# Raspberry_Pi_CM4_Periphery.net
KiCad netlist of a schematic drawn in Altium Designer
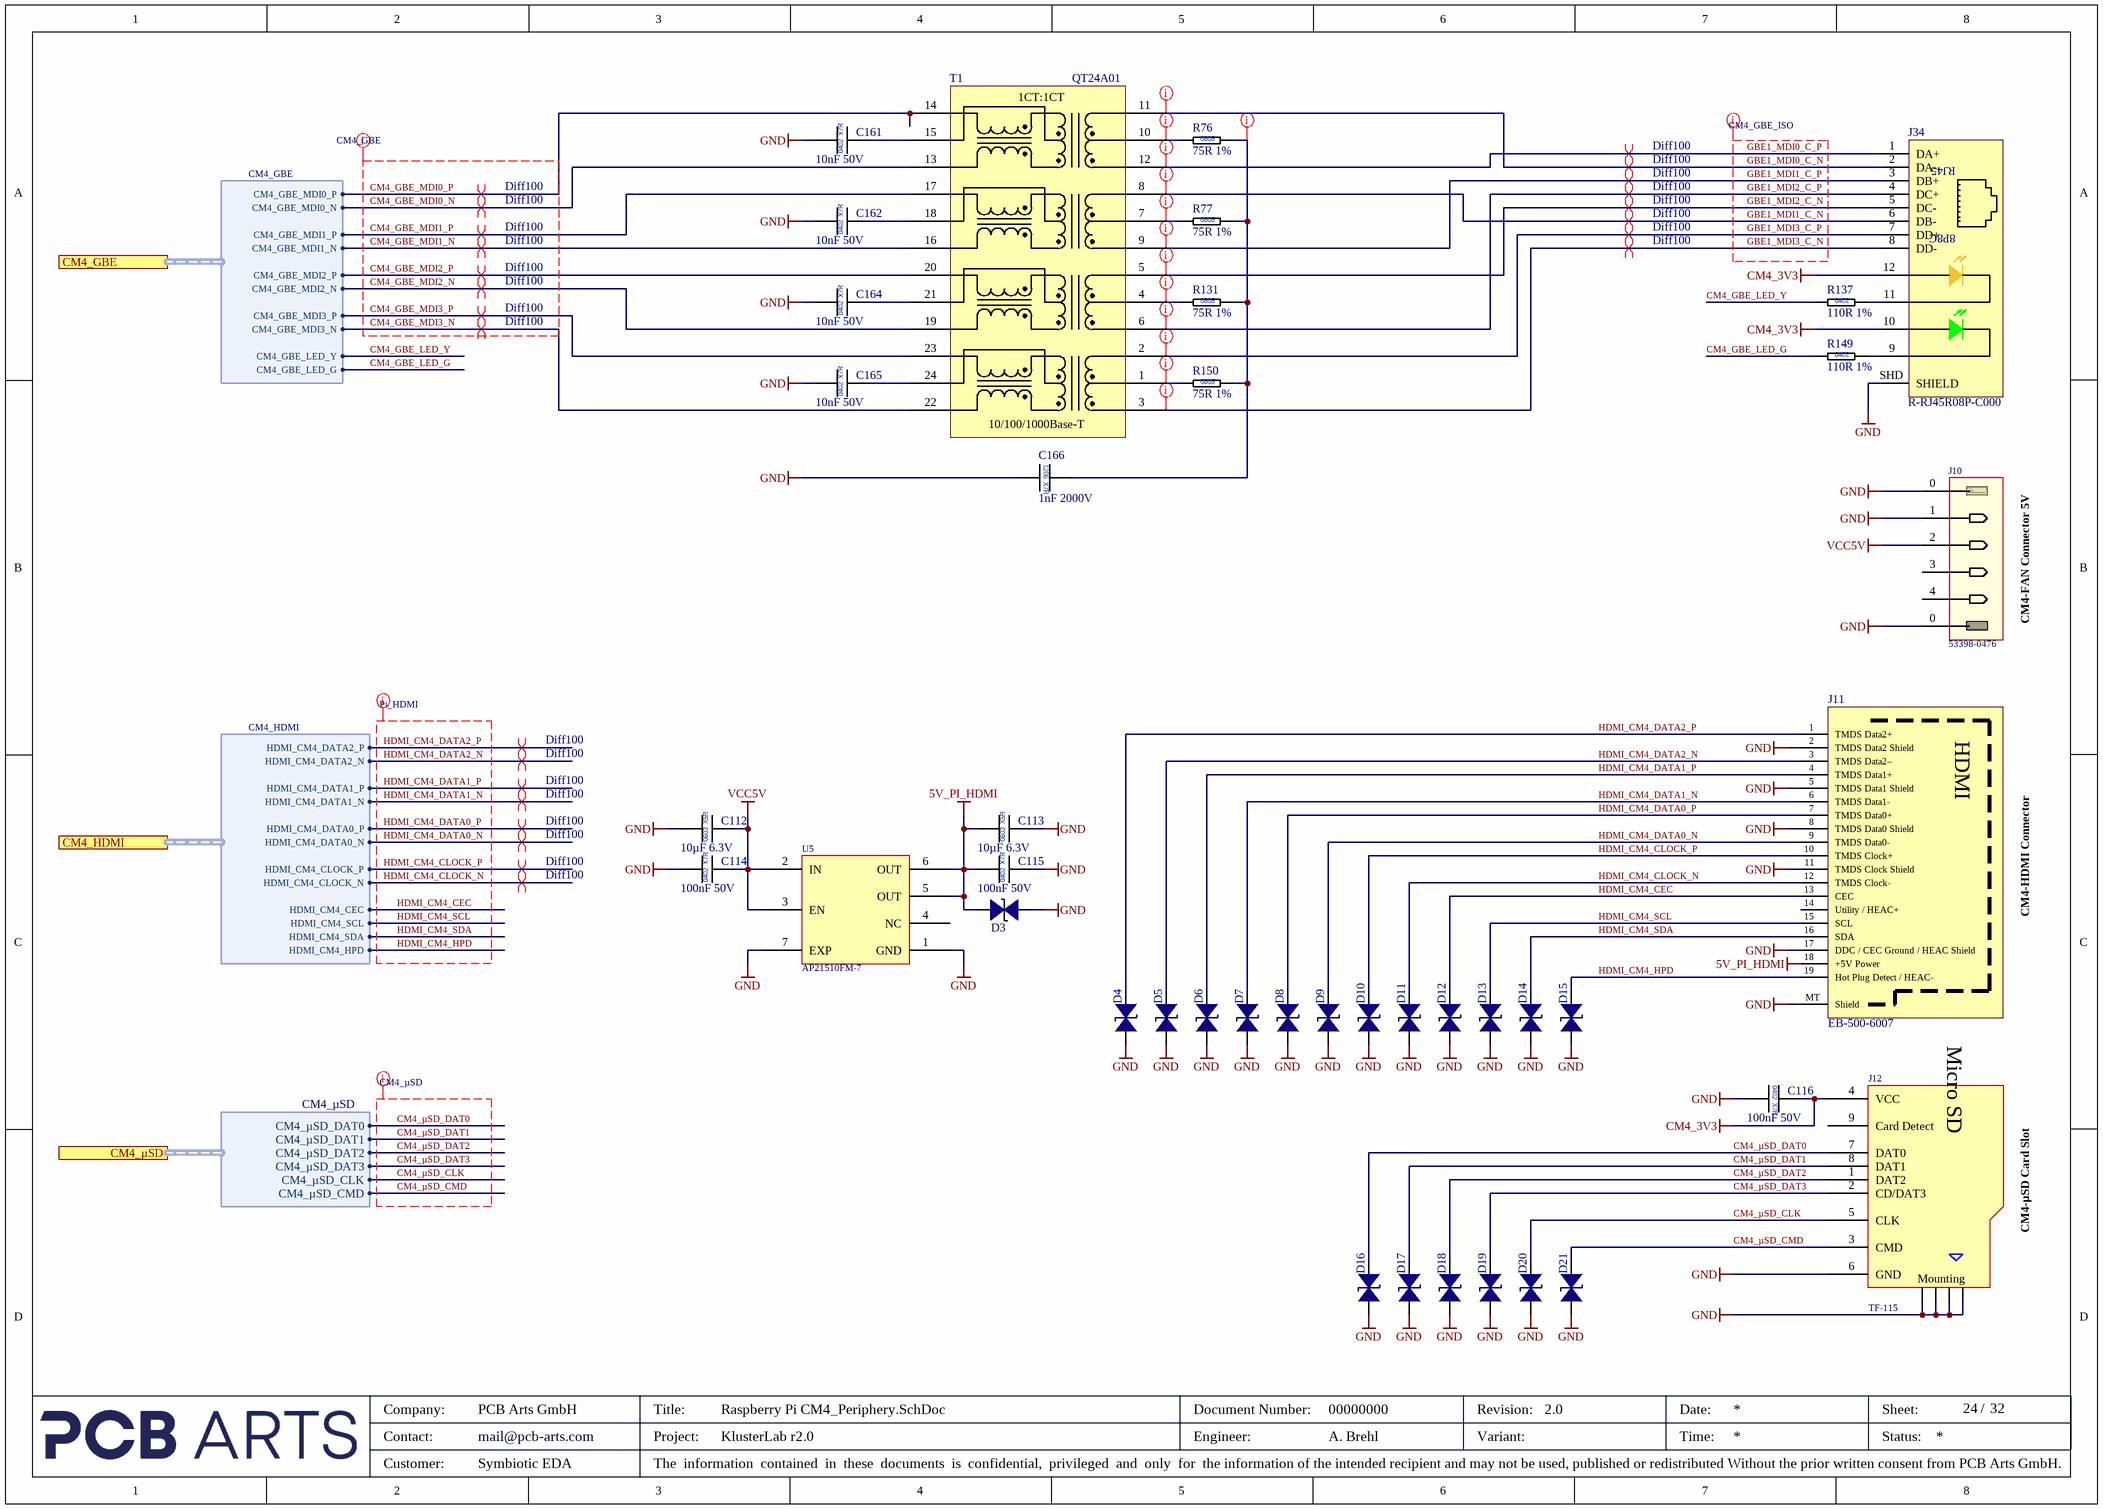
[diagram p0: Raspberry Pi CM4_Periphery.SchDoc]

(export (version "E")
  (design (tool "Eeschema 10.0.6"))
  (components
    (comp (ref "C112")
      (value "10µF 6.3V")
      (footprint "Cap:CAP_0603_L")
      (description "Multilayer Ceramic Capacitors MLCC - SMD/SMT 0603 6.3VDC")
      (libsource (lib "Cap") (part "CAP_0603_10µF_6.3V"))
    )
    (comp (ref "C113")
      (value "10µF 6.3V")
      (footprint "Cap:CAP_0603_L")
      (description "Multilayer Ceramic Capacitors MLCC - SMD/SMT 0603 6.3VDC")
      (libsource (lib "Cap") (part "CAP_0603_10µF_6.3V"))
    )
    (comp (ref "C114")
      (value "100nF 50V")
      (footprint "Cap:CAP_0402_L")
      (description "Multilayer Ceramic Capacitors MLCC - SMD/SMT 0402 50VDC")
      (libsource (lib "Cap") (part "CAP_0402_100nF_50V"))
    )
    (comp (ref "C115")
      (value "100nF 50V")
      (footprint "Cap:CAP_0402_L")
      (description "Multilayer Ceramic Capacitors MLCC - SMD/SMT 0402 50VDC")
      (libsource (lib "Cap") (part "CAP_0402_100nF_50V"))
    )
    (comp (ref "C116")
      (value "100nF 50V")
      (footprint "Cap:CAP_0402_L")
      (description "Multilayer Ceramic Capacitors MLCC - SMD/SMT 0402 50VDC")
      (libsource (lib "") (part "CAP_0402_100nF_50V_1"))
    )
    (comp (ref "C161")
      (value "10nF 50V")
      (footprint "Cap:CAP_0402_L")
      (description "Multilayer Ceramic Capacitors MLCC - SMD/SMT 0402 50VDC")
      (libsource (lib "Cap") (part "CAP_0402_10nF_50V"))
    )
    (comp (ref "C162")
      (value "10nF 50V")
      (footprint "Cap:CAP_0402_L")
      (description "Multilayer Ceramic Capacitors MLCC - SMD/SMT 0402 50VDC")
      (libsource (lib "Cap") (part "CAP_0402_10nF_50V"))
    )
    (comp (ref "C164")
      (value "10nF 50V")
      (footprint "Cap:CAP_0402_L")
      (description "Multilayer Ceramic Capacitors MLCC - SMD/SMT 0402 50VDC")
      (libsource (lib "Cap") (part "CAP_0402_10nF_50V"))
    )
    (comp (ref "C165")
      (value "10nF 50V")
      (footprint "Cap:CAP_0402_L")
      (description "Multilayer Ceramic Capacitors MLCC - SMD/SMT 0402 50VDC")
      (libsource (lib "Cap") (part "CAP_0402_10nF_50V"))
    )
    (comp (ref "C166")
      (value "1nF 2000V")
      (footprint "Cap:CAP_1206")
      (description "Multilayer Ceramic Capacitors MLCC - SMD/SMT 1206 2000VDC")
      (libsource (lib "Cap") (part "CAP_1206_1nF_2000V"))
    )
    (comp (ref "D3")
      (value "CESDP0402UC5VB")
      (footprint "Protec:TVS_0402")
      (description "Low Capacitance ESD Protection Diode 0402")
      (libsource (lib "Protec") (part "CESDP0402UC5VB_TVS Diode 0402"))
    )
    (comp (ref "D4")
      (value "CESDP0402UC5VB")
      (footprint "Protec:TVS_0402")
      (description "Low Capacitance ESD Protection Diode 0402")
      (libsource (lib "Protec") (part "CESDP0402UC5VB_TVS Diode 0402"))
    )
    (comp (ref "D5")
      (value "CESDP0402UC5VB")
      (footprint "Protec:TVS_0402")
      (description "Low Capacitance ESD Protection Diode 0402")
      (libsource (lib "Protec") (part "CESDP0402UC5VB_TVS Diode 0402"))
    )
    (comp (ref "D6")
      (value "CESDP0402UC5VB")
      (footprint "Protec:TVS_0402")
      (description "Low Capacitance ESD Protection Diode 0402")
      (libsource (lib "Protec") (part "CESDP0402UC5VB_TVS Diode 0402"))
    )
    (comp (ref "D7")
      (value "CESDP0402UC5VB")
      (footprint "Protec:TVS_0402")
      (description "Low Capacitance ESD Protection Diode 0402")
      (libsource (lib "Protec") (part "CESDP0402UC5VB_TVS Diode 0402"))
    )
    (comp (ref "D8")
      (value "CESDP0402UC5VB")
      (footprint "Protec:TVS_0402")
      (description "Low Capacitance ESD Protection Diode 0402")
      (libsource (lib "Protec") (part "CESDP0402UC5VB_TVS Diode 0402"))
    )
    (comp (ref "D9")
      (value "CESDP0402UC5VB")
      (footprint "Protec:TVS_0402")
      (description "Low Capacitance ESD Protection Diode 0402")
      (libsource (lib "Protec") (part "CESDP0402UC5VB_TVS Diode 0402"))
    )
    (comp (ref "D10")
      (value "CESDP0402UC5VB")
      (footprint "Protec:TVS_0402")
      (description "Low Capacitance ESD Protection Diode 0402")
      (libsource (lib "Protec") (part "CESDP0402UC5VB_TVS Diode 0402"))
    )
    (comp (ref "D11")
      (value "CESDP0402UC5VB")
      (footprint "Protec:TVS_0402")
      (description "Low Capacitance ESD Protection Diode 0402")
      (libsource (lib "Protec") (part "CESDP0402UC5VB_TVS Diode 0402"))
    )
    (comp (ref "D12")
      (value "CESDP0402UC5VB")
      (footprint "Protec:TVS_0402")
      (description "Low Capacitance ESD Protection Diode 0402")
      (libsource (lib "Protec") (part "CESDP0402UC5VB_TVS Diode 0402"))
    )
    (comp (ref "D13")
      (value "CESDP0402UC5VB")
      (footprint "Protec:TVS_0402")
      (description "Low Capacitance ESD Protection Diode 0402")
      (libsource (lib "Protec") (part "CESDP0402UC5VB_TVS Diode 0402"))
    )
    (comp (ref "D14")
      (value "CESDP0402UC5VB")
      (footprint "Protec:TVS_0402")
      (description "Low Capacitance ESD Protection Diode 0402")
      (libsource (lib "Protec") (part "CESDP0402UC5VB_TVS Diode 0402"))
    )
    (comp (ref "D15")
      (value "CESDP0402UC5VB")
      (footprint "Protec:TVS_0402")
      (description "Low Capacitance ESD Protection Diode 0402")
      (libsource (lib "Protec") (part "CESDP0402UC5VB_TVS Diode 0402"))
    )
    (comp (ref "D16")
      (value "CESDP0402UC5VB")
      (footprint "Protec:TVS_0402")
      (description "Low Capacitance ESD Protection Diode 0402")
      (libsource (lib "Protec") (part "CESDP0402UC5VB_TVS Diode 0402"))
    )
    (comp (ref "D17")
      (value "CESDP0402UC5VB")
      (footprint "Protec:TVS_0402")
      (description "Low Capacitance ESD Protection Diode 0402")
      (libsource (lib "Protec") (part "CESDP0402UC5VB_TVS Diode 0402"))
    )
    (comp (ref "D18")
      (value "CESDP0402UC5VB")
      (footprint "Protec:TVS_0402")
      (description "Low Capacitance ESD Protection Diode 0402")
      (libsource (lib "Protec") (part "CESDP0402UC5VB_TVS Diode 0402"))
    )
    (comp (ref "D19")
      (value "CESDP0402UC5VB")
      (footprint "Protec:TVS_0402")
      (description "Low Capacitance ESD Protection Diode 0402")
      (libsource (lib "Protec") (part "CESDP0402UC5VB_TVS Diode 0402"))
    )
    (comp (ref "D20")
      (value "CESDP0402UC5VB")
      (footprint "Protec:TVS_0402")
      (description "Low Capacitance ESD Protection Diode 0402")
      (libsource (lib "Protec") (part "CESDP0402UC5VB_TVS Diode 0402"))
    )
    (comp (ref "D21")
      (value "CESDP0402UC5VB")
      (footprint "Protec:TVS_0402")
      (description "Low Capacitance ESD Protection Diode 0402")
      (libsource (lib "Protec") (part "CESDP0402UC5VB_TVS Diode 0402"))
    )
    (comp (ref "J10")
      (value "53398-0476")
      (footprint "Conn:Molex 53398-0476")
      (description "1.25mm Pitch, PicoBlade PCB Header, Single Row, horizontal, SMD, 4 Pin")
      (libsource (lib "Conn") (part "53398-0476_1.25mm Pitch, PicoBlade PCB Header, Single Row, horizontal, SMD, 4 Pin"))
    )
    (comp (ref "J11")
      (value "EB-500-6007")
      (footprint "Conn:Elecbee EB-500-6007")
      (description "HDMI Connector Female Vertical 19 Pin")
      (libsource (lib "Conn") (part "EB-500-6007_HDMI Connector 19Pin Vertical THT"))
    )
    (comp (ref "J12")
      (value "TF-115")
      (footprint "conn:TF-115")
      (description "microSD™ Memory Card 8 connector&Ejector 14.5x14.75x1.85mm Card Sockets Connector")
      (libsource (lib "Conn") (part "TF-115_microSD™ Memory Card 8 connector"))
    )
    (comp (ref "J34")
      (value "R-RJ45R08P-C000")
      (footprint "Conn:Ckmtw - R-RJ45R08P-C000")
      (libsource (lib "Conn") (part "R-RJ45R08P-C000_RJ45 8P8C Shielded Yellow - Green Through Hole Ethernet Connectors"))
    )
    (comp (ref "R76")
      (value "75R 1%")
      (footprint "Res:RES_0805")
      (description "Thick Film Resistors - SMD 75Ohm 1%")
      (libsource (lib "Res") (part "RES_0805_75R_1%"))
    )
    (comp (ref "R77")
      (value "75R 1%")
      (footprint "Res:RES_0805")
      (description "Thick Film Resistors - SMD 75Ohm 1%")
      (libsource (lib "Res") (part "RES_0805_75R_1%"))
    )
    (comp (ref "R131")
      (value "75R 1%")
      (footprint "Res:RES_0805")
      (description "Thick Film Resistors - SMD 75Ohm 1%")
      (libsource (lib "Res") (part "RES_0805_75R_1%"))
    )
    (comp (ref "R137")
      (value "110R 1%")
      (footprint "Res:RES_0402_L")
      (description "Thick Film Resistors - SMD 110Ohm 1%")
      (libsource (lib "Res") (part "RES_0402_110R_1%"))
    )
    (comp (ref "R149")
      (value "110R 1%")
      (footprint "Res:RES_0402_L")
      (description "Thick Film Resistors - SMD 110Ohm 1%")
      (libsource (lib "Res") (part "RES_0402_110R_1%"))
    )
    (comp (ref "R150")
      (value "75R 1%")
      (footprint "Res:RES_0805")
      (description "Thick Film Resistors - SMD 75Ohm 1%")
      (libsource (lib "Res") (part "RES_0805_75R_1%"))
    )
    (comp (ref "T1")
      (value "QT24A01")
      (footprint "Indc:QT24A01")
      (description "1:1 350 28 1.2 -1 -16 SMD,24PIN RJ45 Transformer RoHS")
      (libsource (lib "Indc") (part "QT24A01_10/100/1000Base-T  Single  Port  Transformer"))
    )
    (comp (ref "U5")
      (value "AP21510FM-7")
      (footprint "Power:QFN50P201X181X60_HS-7N")
      (description "Power Switch ICs - Power Distribution 0.5A SGL Ch USB 2.0 Curr Limited Switch")
      (libsource (lib "Power") (part "AP21510FM-7_Power Switch ICs - Power Distribution Load Switch"))
    )
  )
  (nets
    (net (code "4") (name "/CM4_GBE_LED_G") (class "Default")
      (node (ref "R149") (pin "1") (pinfunction "1_1") (pintype "passive"))
    )
    (net (code "5") (name "/CM4_GBE_LED_Y") (class "Default")
      (node (ref "R137") (pin "1") (pinfunction "1_1") (pintype "passive"))
    )
    (net (code "6") (name "/CM4_GBE_MDI0_N") (class "Default")
      (node (ref "T1") (pin "13") (pinfunction "MX4-_13") (pintype "passive"))
    )
    (net (code "7") (name "/CM4_GBE_MDI0_P") (class "Default")
      (node (ref "T1") (pin "14") (pinfunction "MX4+_14") (pintype "passive"))
    )
    (net (code "8") (name "/CM4_GBE_MDI1_N") (class "Default")
      (node (ref "T1") (pin "16") (pinfunction "MX3-_16") (pintype "passive"))
    )
    (net (code "9") (name "/CM4_GBE_MDI1_P") (class "Default")
      (node (ref "T1") (pin "17") (pinfunction "MX3+_17") (pintype "passive"))
    )
    (net (code "10") (name "/CM4_GBE_MDI2_N") (class "Default")
      (node (ref "T1") (pin "19") (pinfunction "MX2-_19") (pintype "passive"))
    )
    (net (code "11") (name "/CM4_GBE_MDI2_P") (class "Default")
      (node (ref "T1") (pin "20") (pinfunction "MX2+_20") (pintype "passive"))
    )
    (net (code "12") (name "/CM4_GBE_MDI3_N") (class "Default")
      (node (ref "T1") (pin "22") (pinfunction "MX1-_22") (pintype "passive"))
    )
    (net (code "13") (name "/CM4_GBE_MDI3_P") (class "Default")
      (node (ref "T1") (pin "23") (pinfunction "MX1+_23") (pintype "passive"))
    )
    (net (code "14") (name "/CM4_µSD_CLK") (class "Default")
      (node (ref "D20") (pin "2") (pinfunction "2_2") (pintype "passive"))
      (node (ref "J12") (pin "5") (pinfunction "CLK_5") (pintype "passive"))
    )
    (net (code "15") (name "/CM4_µSD_CMD") (class "Default")
      (node (ref "D21") (pin "2") (pinfunction "2_2") (pintype "passive"))
      (node (ref "J12") (pin "3") (pinfunction "CMD_3") (pintype "passive"))
    )
    (net (code "16") (name "/CM4_µSD_DAT0") (class "Default")
      (node (ref "D16") (pin "2") (pinfunction "2_2") (pintype "passive"))
      (node (ref "J12") (pin "7") (pinfunction "DAT0_7") (pintype "passive"))
    )
    (net (code "17") (name "/CM4_µSD_DAT1") (class "Default")
      (node (ref "D17") (pin "2") (pinfunction "2_2") (pintype "passive"))
      (node (ref "J12") (pin "8") (pinfunction "DAT1_8") (pintype "passive"))
    )
    (net (code "18") (name "/CM4_µSD_DAT2") (class "Default")
      (node (ref "D18") (pin "2") (pinfunction "2_2") (pintype "passive"))
      (node (ref "J12") (pin "1") (pinfunction "DAT2_1") (pintype "passive"))
    )
    (net (code "19") (name "/CM4_µSD_DAT3") (class "Default")
      (node (ref "D19") (pin "2") (pinfunction "2_2") (pintype "passive"))
      (node (ref "J12") (pin "2") (pinfunction "CD/DAT3_2") (pintype "passive"))
    )
    (net (code "20") (name "/GBE1_MDI0_C_N") (class "Default")
      (node (ref "J34") (pin "2") (pinfunction "DA-_2") (pintype "passive"))
      (node (ref "T1") (pin "11") (pinfunction "TD4+_11") (pintype "passive"))
    )
    (net (code "21") (name "/GBE1_MDI0_C_P") (class "Default")
      (node (ref "J34") (pin "1") (pinfunction "DA+_1") (pintype "passive"))
      (node (ref "T1") (pin "12") (pinfunction "TD4-_12") (pintype "passive"))
    )
    (net (code "22") (name "/GBE1_MDI1_C_N") (class "Default")
      (node (ref "J34") (pin "6") (pinfunction "DB-_6") (pintype "passive"))
      (node (ref "T1") (pin "8") (pinfunction "TD3+_8") (pintype "passive"))
    )
    (net (code "23") (name "/GBE1_MDI1_C_P") (class "Default")
      (node (ref "J34") (pin "3") (pinfunction "DB+_3") (pintype "passive"))
      (node (ref "T1") (pin "9") (pinfunction "TD3-_9") (pintype "passive"))
    )
    (net (code "24") (name "/GBE1_MDI2_C_N") (class "Default")
      (node (ref "J34") (pin "5") (pinfunction "DC-_5") (pintype "passive"))
      (node (ref "T1") (pin "5") (pinfunction "TD2+_5") (pintype "passive"))
    )
    (net (code "25") (name "/GBE1_MDI2_C_P") (class "Default")
      (node (ref "J34") (pin "4") (pinfunction "DC+_4") (pintype "passive"))
      (node (ref "T1") (pin "6") (pinfunction "TD2-_6") (pintype "passive"))
    )
    (net (code "26") (name "/GBE1_MDI3_C_N") (class "Default")
      (node (ref "J34") (pin "8") (pinfunction "DD-_8") (pintype "passive"))
      (node (ref "T1") (pin "3") (pinfunction "TD1-_3") (pintype "passive"))
    )
    (net (code "27") (name "/GBE1_MDI3_C_P") (class "Default")
      (node (ref "J34") (pin "7") (pinfunction "DD+_7") (pintype "passive"))
      (node (ref "T1") (pin "2") (pinfunction "TD1+_2") (pintype "passive"))
    )
    (net (code "28") (name "/HDMI_CM4_CEC") (class "Default")
      (node (ref "D12") (pin "2") (pinfunction "2_2") (pintype "passive"))
      (node (ref "J11") (pin "13") (pinfunction "CEC_13") (pintype "passive"))
    )
    (net (code "29") (name "/HDMI_CM4_CLOCK_N") (class "Default")
      (node (ref "D11") (pin "2") (pinfunction "2_2") (pintype "passive"))
      (node (ref "J11") (pin "12") (pinfunction "TMDS_Clock-_12") (pintype "passive"))
    )
    (net (code "30") (name "/HDMI_CM4_CLOCK_P") (class "Default")
      (node (ref "D10") (pin "2") (pinfunction "2_2") (pintype "passive"))
      (node (ref "J11") (pin "10") (pinfunction "TMDS_Clock+_10") (pintype "passive"))
    )
    (net (code "31") (name "/HDMI_CM4_DATA0_N") (class "Default")
      (node (ref "D9") (pin "2") (pinfunction "2_2") (pintype "passive"))
      (node (ref "J11") (pin "9") (pinfunction "TMDS_Data0-_9") (pintype "passive"))
    )
    (net (code "32") (name "/HDMI_CM4_DATA0_P") (class "Default")
      (node (ref "D8") (pin "2") (pinfunction "2_2") (pintype "passive"))
      (node (ref "J11") (pin "7") (pinfunction "TMDS_Data0+_7") (pintype "passive"))
    )
    (net (code "33") (name "/HDMI_CM4_DATA1_N") (class "Default")
      (node (ref "D7") (pin "2") (pinfunction "2_2") (pintype "passive"))
      (node (ref "J11") (pin "6") (pinfunction "TMDS_Data1-_6") (pintype "passive"))
    )
    (net (code "34") (name "/HDMI_CM4_DATA1_P") (class "Default")
      (node (ref "D6") (pin "2") (pinfunction "2_2") (pintype "passive"))
      (node (ref "J11") (pin "4") (pinfunction "TMDS_Data1+_4") (pintype "passive"))
    )
    (net (code "35") (name "/HDMI_CM4_DATA2_N") (class "Default")
      (node (ref "D5") (pin "2") (pinfunction "2_2") (pintype "passive"))
      (node (ref "J11") (pin "3") (pinfunction "TMDS_Data2–_3") (pintype "passive"))
    )
    (net (code "36") (name "/HDMI_CM4_DATA2_P") (class "Default")
      (node (ref "D4") (pin "2") (pinfunction "2_2") (pintype "passive"))
      (node (ref "J11") (pin "1") (pinfunction "TMDS_Data2+_1") (pintype "passive"))
    )
    (net (code "37") (name "/HDMI_CM4_HPD") (class "Default")
      (node (ref "D15") (pin "2") (pinfunction "2_2") (pintype "passive"))
      (node (ref "J11") (pin "19") (pinfunction "Hot_Plug_Detect_/_HEAC-_19") (pintype "passive"))
    )
    (net (code "38") (name "/HDMI_CM4_SCL") (class "Default")
      (node (ref "D13") (pin "2") (pinfunction "2_2") (pintype "passive"))
      (node (ref "J11") (pin "15") (pinfunction "SCL_15") (pintype "passive"))
    )
    (net (code "39") (name "/HDMI_CM4_SDA") (class "Default")
      (node (ref "D14") (pin "2") (pinfunction "2_2") (pintype "passive"))
      (node (ref "J11") (pin "16") (pinfunction "SDA_16") (pintype "passive"))
    )
    (net (code "43") (name "5V_PI_HDMI") (class "Default")
      (node (ref "C113") (pin "1") (pinfunction "1_1") (pintype "passive"))
      (node (ref "C115") (pin "1") (pinfunction "1_1") (pintype "passive"))
      (node (ref "D3") (pin "1") (pinfunction "1_1") (pintype "passive"))
      (node (ref "J11") (pin "18") (pinfunction "+5V_Power_18") (pintype "passive"))
      (node (ref "U5") (pin "5") (pinfunction "OUT_5") (pintype "power_in"))
      (node (ref "U5") (pin "6") (pinfunction "OUT_6") (pintype "power_in"))
    )
    (net (code "44") (name "CM4_3V3") (class "Default")
      (node (ref "C116") (pin "1") (pinfunction "1_1") (pintype "passive"))
      (node (ref "J12") (pin "4") (pinfunction "VCC_4") (pintype "passive"))
      (node (ref "J34") (pin "10") (pinfunction "10_10") (pintype "passive"))
      (node (ref "J34") (pin "12") (pinfunction "12_12") (pintype "passive"))
    )
    (net (code "45") (name "GND") (class "Default")
      (node (ref "C112") (pin "1") (pinfunction "1_1") (pintype "passive"))
      (node (ref "C113") (pin "2") (pinfunction "2_2") (pintype "passive"))
      (node (ref "C114") (pin "1") (pinfunction "1_1") (pintype "passive"))
      (node (ref "C115") (pin "2") (pinfunction "2_2") (pintype "passive"))
      (node (ref "C116") (pin "2") (pinfunction "2_2") (pintype "passive"))
      (node (ref "C161") (pin "1") (pinfunction "1_1") (pintype "passive"))
      (node (ref "C162") (pin "1") (pinfunction "1_1") (pintype "passive"))
      (node (ref "C164") (pin "1") (pinfunction "1_1") (pintype "passive"))
      (node (ref "C165") (pin "1") (pinfunction "1_1") (pintype "passive"))
      (node (ref "C166") (pin "2") (pinfunction "2_2") (pintype "passive"))
      (node (ref "D10") (pin "1") (pinfunction "1_1") (pintype "passive"))
      (node (ref "D11") (pin "1") (pinfunction "1_1") (pintype "passive"))
      (node (ref "D12") (pin "1") (pinfunction "1_1") (pintype "passive"))
      (node (ref "D13") (pin "1") (pinfunction "1_1") (pintype "passive"))
      (node (ref "D14") (pin "1") (pinfunction "1_1") (pintype "passive"))
      (node (ref "D15") (pin "1") (pinfunction "1_1") (pintype "passive"))
      (node (ref "D16") (pin "1") (pinfunction "1_1") (pintype "passive"))
      (node (ref "D17") (pin "1") (pinfunction "1_1") (pintype "passive"))
      (node (ref "D18") (pin "1") (pinfunction "1_1") (pintype "passive"))
      (node (ref "D19") (pin "1") (pinfunction "1_1") (pintype "passive"))
      (node (ref "D20") (pin "1") (pinfunction "1_1") (pintype "passive"))
      (node (ref "D21") (pin "1") (pinfunction "1_1") (pintype "passive"))
      (node (ref "D3") (pin "2") (pinfunction "2_2") (pintype "passive"))
      (node (ref "D4") (pin "1") (pinfunction "1_1") (pintype "passive"))
      (node (ref "D5") (pin "1") (pinfunction "1_1") (pintype "passive"))
      (node (ref "D6") (pin "1") (pinfunction "1_1") (pintype "passive"))
      (node (ref "D7") (pin "1") (pinfunction "1_1") (pintype "passive"))
      (node (ref "D8") (pin "1") (pinfunction "1_1") (pintype "passive"))
      (node (ref "D9") (pin "1") (pinfunction "1_1") (pintype "passive"))
      (node (ref "J10") (pin "0") (pinfunction "0_0") (pintype "passive"))
      (node (ref "J10") (pin "1") (pinfunction "1_1") (pintype "passive"))
      (node (ref "J11") (pin "11") (pinfunction "TMDS_Clock_Shield_11") (pintype "passive"))
      (node (ref "J11") (pin "17") (pinfunction "DDC_/_CEC_Ground_/_HEAC_Shield_17") (pintype "passive"))
      (node (ref "J11") (pin "2") (pinfunction "TMDS_Data2_Shield_2") (pintype "passive"))
      (node (ref "J11") (pin "5") (pinfunction "TMDS_Data1_Shield_5") (pintype "passive"))
      (node (ref "J11") (pin "8") (pinfunction "TMDS_Data0_Shield_8") (pintype "passive"))
      (node (ref "J11") (pin "MT") (pinfunction "Shield_MT") (pintype "passive"))
      (node (ref "J12") (pin "10") (pinfunction "10_10") (pintype "passive"))
      (node (ref "J12") (pin "11") (pinfunction "11_11") (pintype "passive"))
      (node (ref "J12") (pin "12") (pinfunction "12_12") (pintype "passive"))
      (node (ref "J12") (pin "13") (pinfunction "13_13") (pintype "passive"))
      (node (ref "J12") (pin "6") (pinfunction "GND_6") (pintype "passive"))
      (node (ref "J34") (pin "SHD") (pinfunction "SHIELD_SHD") (pintype "passive"))
      (node (ref "U5") (pin "1") (pinfunction "GND_1") (pintype "power_in"))
      (node (ref "U5") (pin "7") (pinfunction "EXP_7") (pintype "power_in"))
    )
    (net (code "46") (name "Net-(C166-Pad1)") (class "Default")
      (node (ref "C166") (pin "1") (pinfunction "1_1") (pintype "passive"))
      (node (ref "R131") (pin "2") (pinfunction "2_2") (pintype "passive"))
      (node (ref "R150") (pin "2") (pinfunction "2_2") (pintype "passive"))
      (node (ref "R76") (pin "2") (pinfunction "2_2") (pintype "passive"))
      (node (ref "R77") (pin "2") (pinfunction "2_2") (pintype "passive"))
    )
    (net (code "47") (name "Net-(J34-Pad9)") (class "Default")
      (node (ref "J34") (pin "9") (pinfunction "9_9") (pintype "passive"))
      (node (ref "R149") (pin "2") (pinfunction "2_2") (pintype "passive"))
    )
    (net (code "48") (name "Net-(J34-Pad11)") (class "Default")
      (node (ref "J34") (pin "11") (pinfunction "11_11") (pintype "passive"))
      (node (ref "R137") (pin "2") (pinfunction "2_2") (pintype "passive"))
    )
    (net (code "49") (name "Net-(T1-MCT1)") (class "Default")
      (node (ref "C165") (pin "2") (pinfunction "2_2") (pintype "passive"))
      (node (ref "T1") (pin "24") (pinfunction "MCT1_24") (pintype "passive"))
    )
    (net (code "50") (name "Net-(T1-MCT2)") (class "Default")
      (node (ref "C164") (pin "2") (pinfunction "2_2") (pintype "passive"))
      (node (ref "T1") (pin "21") (pinfunction "MCT2_21") (pintype "passive"))
    )
    (net (code "51") (name "Net-(T1-MCT3)") (class "Default")
      (node (ref "C162") (pin "2") (pinfunction "2_2") (pintype "passive"))
      (node (ref "T1") (pin "18") (pinfunction "MCT3_18") (pintype "passive"))
    )
    (net (code "52") (name "Net-(T1-MCT4)") (class "Default")
      (node (ref "C161") (pin "2") (pinfunction "2_2") (pintype "passive"))
      (node (ref "T1") (pin "15") (pinfunction "MCT4_15") (pintype "passive"))
    )
    (net (code "53") (name "Net-(T1-TCT1)") (class "Default")
      (node (ref "R150") (pin "1") (pinfunction "1_1") (pintype "passive"))
      (node (ref "T1") (pin "1") (pinfunction "TCT1_1") (pintype "passive"))
    )
    (net (code "54") (name "Net-(T1-TCT2)") (class "Default")
      (node (ref "R131") (pin "1") (pinfunction "1_1") (pintype "passive"))
      (node (ref "T1") (pin "4") (pinfunction "TCT2_4") (pintype "passive"))
    )
    (net (code "55") (name "Net-(T1-TCT3)") (class "Default")
      (node (ref "R77") (pin "1") (pinfunction "1_1") (pintype "passive"))
      (node (ref "T1") (pin "7") (pinfunction "TCT3_7") (pintype "passive"))
    )
    (net (code "56") (name "Net-(T1-TCT4)") (class "Default")
      (node (ref "R76") (pin "1") (pinfunction "1_1") (pintype "passive"))
      (node (ref "T1") (pin "10") (pinfunction "TCT4_10") (pintype "passive"))
    )
    (net (code "57") (name "VCC5V") (class "Default")
      (node (ref "C112") (pin "2") (pinfunction "2_2") (pintype "passive"))
      (node (ref "C114") (pin "2") (pinfunction "2_2") (pintype "passive"))
      (node (ref "J10") (pin "2") (pinfunction "2_2") (pintype "passive"))
      (node (ref "U5") (pin "2") (pinfunction "IN_2") (pintype "power_in"))
      (node (ref "U5") (pin "3") (pinfunction "EN_3") (pintype "power_in"))
    )
    (net (code "58") (name "unconnected-(J10-Pad3)") (class "Default")
      (node (ref "J10") (pin "3") (pinfunction "3_3") (pintype "passive"))
    )
    (net (code "59") (name "unconnected-(J10-Pad4)") (class "Default")
      (node (ref "J10") (pin "4") (pinfunction "4_4") (pintype "passive"))
    )
    (net (code "60") (name "unconnected-(J11-Utility_{slash}_HEAC+-Pad14)") (class "Default")
      (node (ref "J11") (pin "14") (pinfunction "Utility_/_HEAC+_14") (pintype "passive"))
    )
    (net (code "61") (name "unconnected-(J12-Card_Detect-Pad9)") (class "Default")
      (node (ref "J12") (pin "9") (pinfunction "Card_Detect_9") (pintype "passive"))
    )
    (net (code "62") (name "unconnected-(U5-NC-Pad4)") (class "Default")
      (node (ref "U5") (pin "4") (pinfunction "NC_4") (pintype "power_in"))
    )
  )
)
